# DDR3_2.net
KiCad netlist of a schematic drawn in Altium Designer
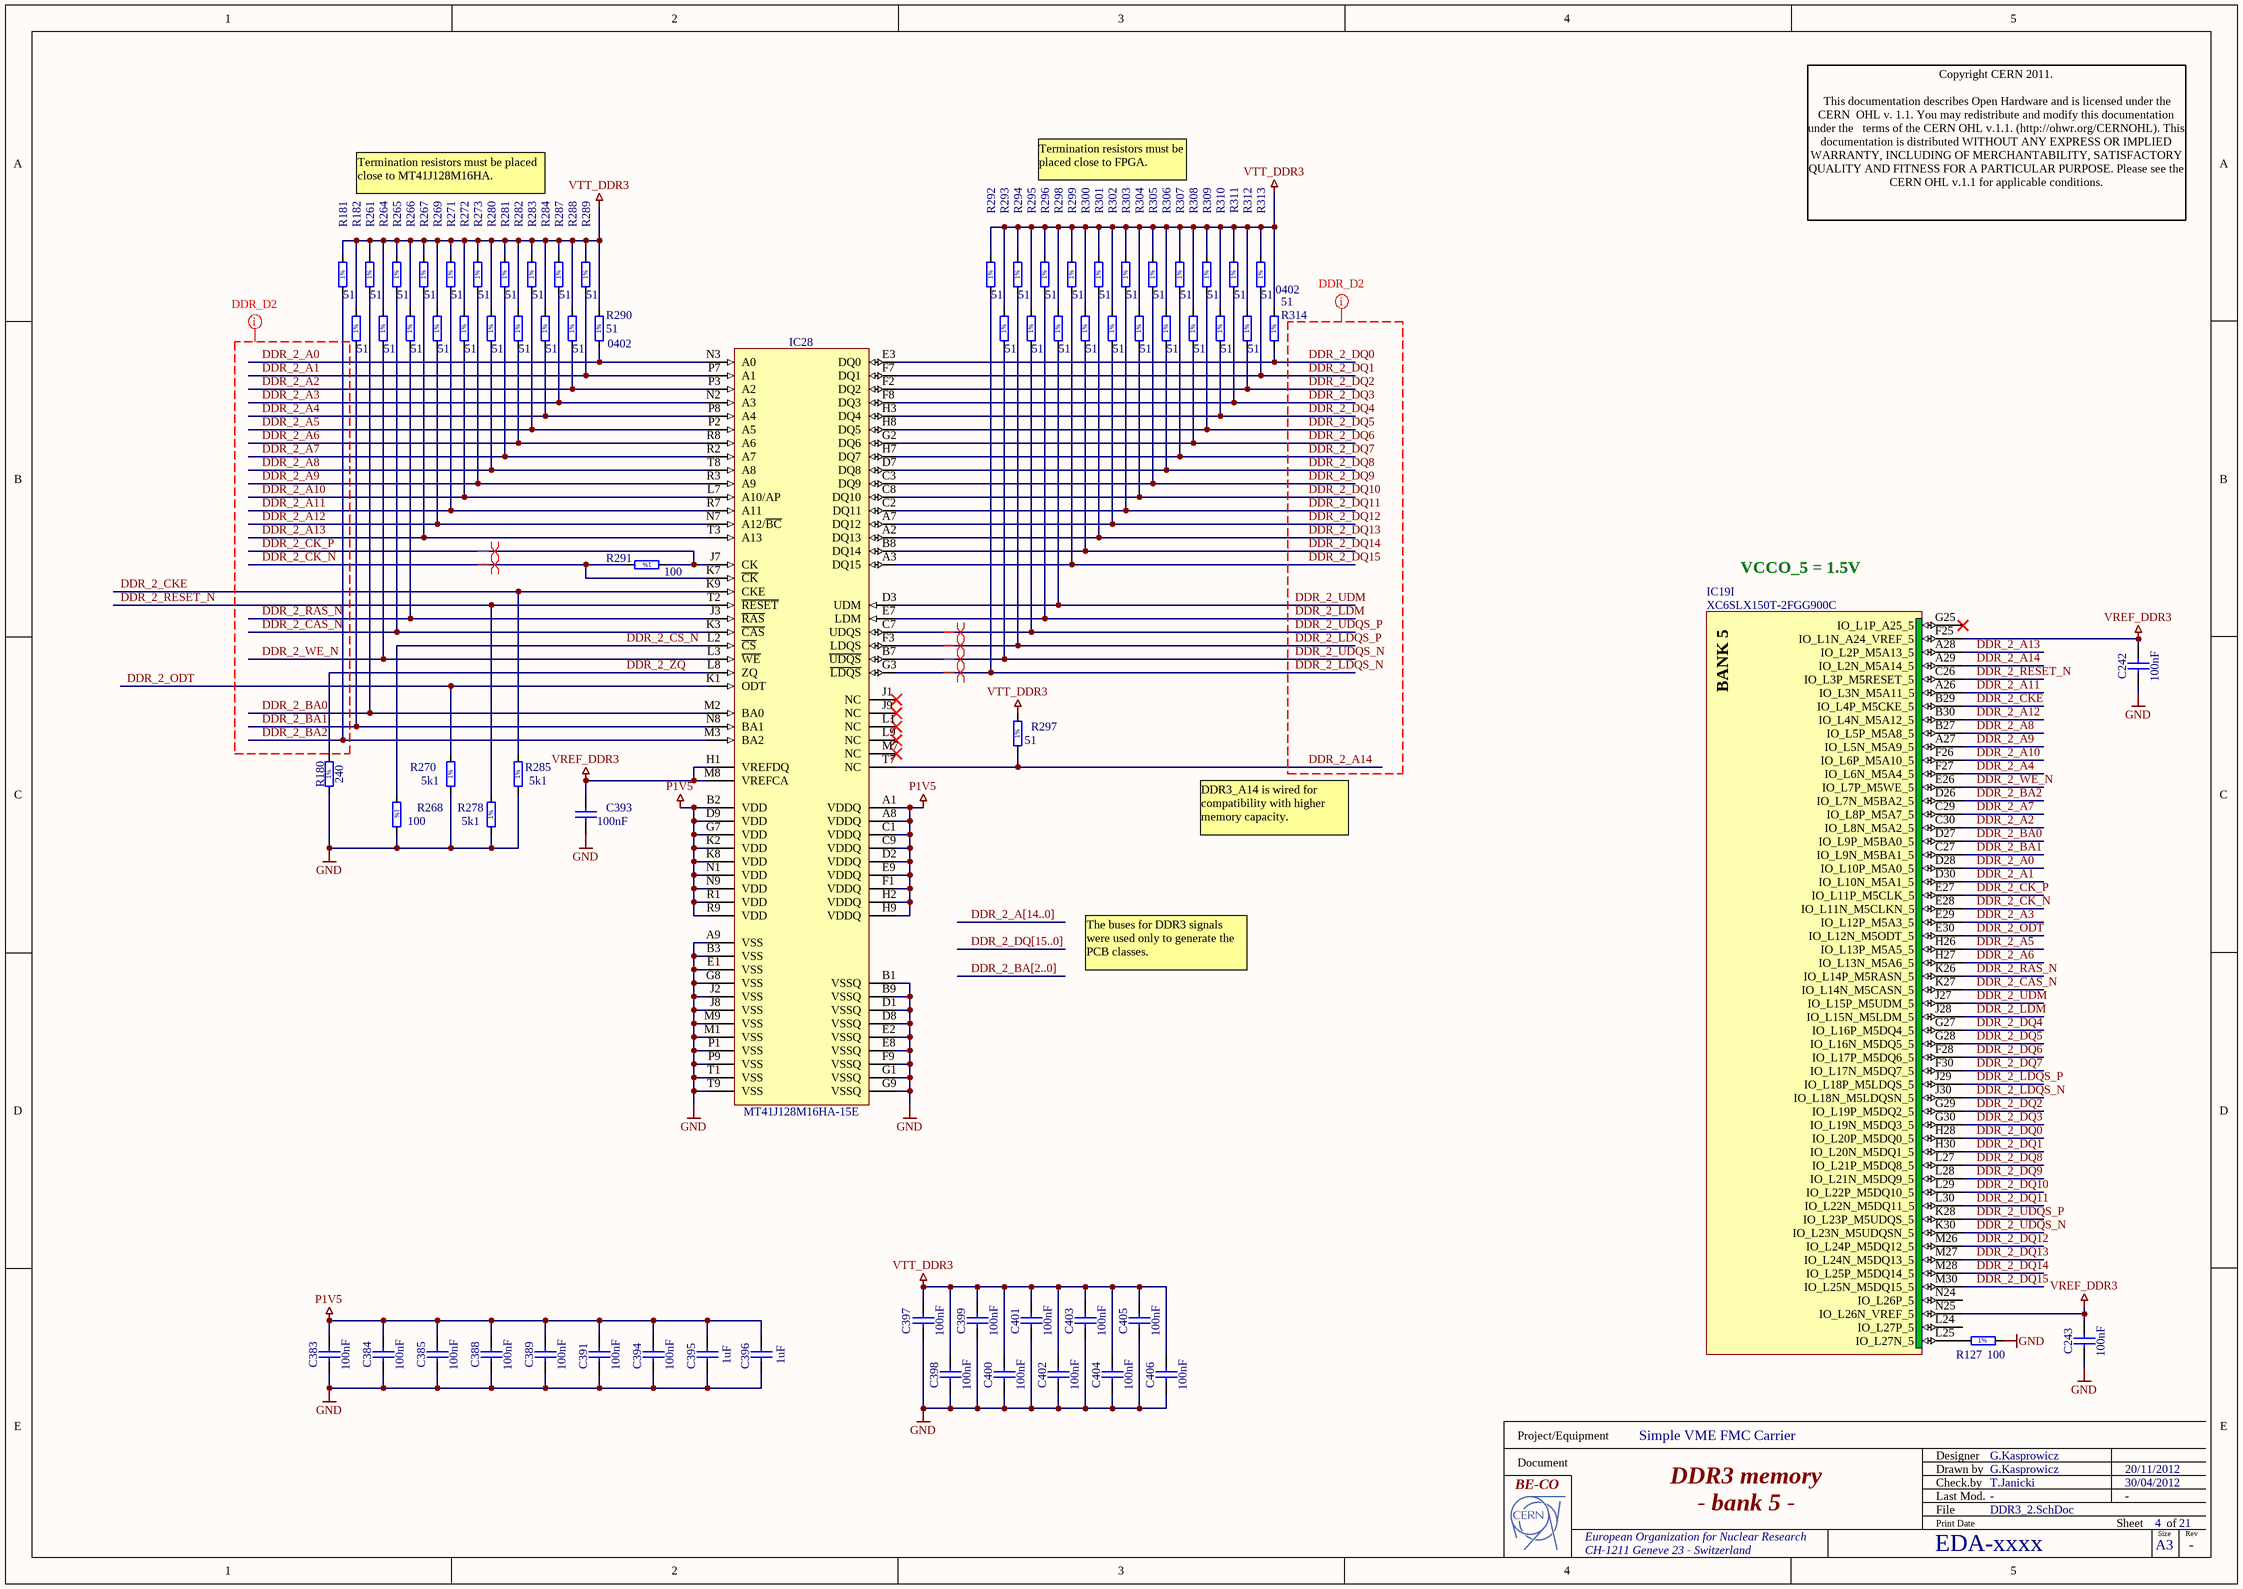
[diagram p0: DDR3_2.SchDoc]

(export (version "E")
  (design (tool "Eeschema 10.0.6"))
  (components
    (comp (ref "C242")
      (value "100nF")
      (footprint "CAPC1005X55N")
      (description "Non-polarised capacitor")
      (fields
        (field (name "PART NUMBER") "CC0402_100NF_16V_10%_X7R")
        (field (name "VOLTAGE") "16V")
        (field (name "AUTHOR") "CERN DEM JLC")
      )
      (libsource (lib "Capacitors") (part "Capacitor - non polarized"))
    )
    (comp (ref "C243")
      (value "100nF")
      (footprint "CAPC1005X55N")
      (description "Non-polarised capacitor")
      (fields
        (field (name "PART NUMBER") "CC0402_100NF_16V_10%_X7R")
        (field (name "VOLTAGE") "16V")
        (field (name "AUTHOR") "CERN DEM JLC")
      )
      (libsource (lib "Capacitors") (part "Capacitor - non polarized"))
    )
    (comp (ref "C383")
      (value "100nF")
      (footprint "CAPC1005X55N")
      (description "Non-polarised capacitor")
      (fields
        (field (name "PART NUMBER") "CC0402_100NF_16V_10%_X7R")
        (field (name "VOLTAGE") "16V")
        (field (name "AUTHOR") "CERN DEM JLC")
      )
      (libsource (lib "Capacitors") (part "Capacitor - non polarized"))
    )
    (comp (ref "C384")
      (value "100nF")
      (footprint "CAPC1005X55N")
      (description "Non-polarised capacitor")
      (fields
        (field (name "PART NUMBER") "CC0402_100NF_16V_10%_X7R")
        (field (name "VOLTAGE") "16V")
        (field (name "AUTHOR") "CERN DEM JLC")
      )
      (libsource (lib "Capacitors") (part "Capacitor - non polarized"))
    )
    (comp (ref "C385")
      (value "100nF")
      (footprint "CAPC1005X55N")
      (description "Non-polarised capacitor")
      (fields
        (field (name "PART NUMBER") "CC0402_100NF_16V_10%_X7R")
        (field (name "VOLTAGE") "16V")
        (field (name "AUTHOR") "CERN DEM JLC")
      )
      (libsource (lib "Capacitors") (part "Capacitor - non polarized"))
    )
    (comp (ref "C388")
      (value "100nF")
      (footprint "CAPC1005X55N")
      (description "Non-polarised capacitor")
      (fields
        (field (name "PART NUMBER") "CC0402_100NF_16V_10%_X7R")
        (field (name "VOLTAGE") "16V")
        (field (name "AUTHOR") "CERN DEM JLC")
      )
      (libsource (lib "Capacitors") (part "Capacitor - non polarized"))
    )
    (comp (ref "C389")
      (value "100nF")
      (footprint "CAPC1005X55N")
      (description "Non-polarised capacitor")
      (fields
        (field (name "PART NUMBER") "CC0402_100NF_16V_10%_X7R")
        (field (name "VOLTAGE") "16V")
        (field (name "AUTHOR") "CERN DEM JLC")
      )
      (libsource (lib "Capacitors") (part "Capacitor - non polarized"))
    )
    (comp (ref "C391")
      (value "100nF")
      (footprint "CAPC1005X55N")
      (description "Non-polarised capacitor")
      (fields
        (field (name "PART NUMBER") "CC0402_100NF_16V_10%_X7R")
        (field (name "VOLTAGE") "16V")
        (field (name "AUTHOR") "CERN DEM JLC")
      )
      (libsource (lib "Capacitors") (part "Capacitor - non polarized"))
    )
    (comp (ref "C393")
      (value "100nF")
      (footprint "CAPC1005X55N")
      (description "Non-polarised capacitor")
      (fields
        (field (name "PART NUMBER") "CC0402_100NF_16V_10%_X7R")
        (field (name "VOLTAGE") "16V")
        (field (name "AUTHOR") "CERN DEM JLC")
      )
      (libsource (lib "Capacitors") (part "Capacitor - non polarized"))
    )
    (comp (ref "C394")
      (value "100nF")
      (footprint "CAPC1005X55N")
      (description "Non-polarised capacitor")
      (fields
        (field (name "PART NUMBER") "CC0402_100NF_16V_10%_X7R")
        (field (name "VOLTAGE") "16V")
        (field (name "AUTHOR") "CERN DEM JLC")
      )
      (libsource (lib "Capacitors") (part "Capacitor - non polarized"))
    )
    (comp (ref "C395")
      (value "1uF")
      (footprint "CAPC1608X87N")
      (description "Non-polarised capacitor")
      (fields
        (field (name "PART NUMBER") "CC0603_1UF_16V_10%_X7R")
        (field (name "VOLTAGE") "16V")
        (field (name "AUTHOR") "CERN DEM JLC")
      )
      (libsource (lib "Capacitors") (part "Capacitor - non polarized"))
    )
    (comp (ref "C396")
      (value "1uF")
      (footprint "CAPC1608X87N")
      (description "Non-polarised capacitor")
      (fields
        (field (name "PART NUMBER") "CC0603_1UF_16V_10%_X7R")
        (field (name "VOLTAGE") "16V")
        (field (name "AUTHOR") "CERN DEM JLC")
      )
      (libsource (lib "Capacitors") (part "Capacitor - non polarized"))
    )
    (comp (ref "C397")
      (value "100nF")
      (footprint "CAPC1005X55N")
      (description "Non-polarised capacitor")
      (fields
        (field (name "PART NUMBER") "CC0402_100NF_16V_10%_X7R")
        (field (name "VOLTAGE") "16V")
        (field (name "AUTHOR") "CERN DEM JLC")
      )
      (libsource (lib "Capacitors") (part "Capacitor - non polarized"))
    )
    (comp (ref "C398")
      (value "100nF")
      (footprint "CAPC1005X55N")
      (description "Non-polarised capacitor")
      (fields
        (field (name "PART NUMBER") "CC0402_100NF_16V_10%_X7R")
        (field (name "VOLTAGE") "16V")
        (field (name "AUTHOR") "CERN DEM JLC")
      )
      (libsource (lib "Capacitors") (part "Capacitor - non polarized"))
    )
    (comp (ref "C399")
      (value "100nF")
      (footprint "CAPC1005X55N")
      (description "Non-polarised capacitor")
      (fields
        (field (name "PART NUMBER") "CC0402_100NF_16V_10%_X7R")
        (field (name "VOLTAGE") "16V")
        (field (name "AUTHOR") "CERN DEM JLC")
      )
      (libsource (lib "Capacitors") (part "Capacitor - non polarized"))
    )
    (comp (ref "C400")
      (value "100nF")
      (footprint "CAPC1005X55N")
      (description "Non-polarised capacitor")
      (fields
        (field (name "PART NUMBER") "CC0402_100NF_16V_10%_X7R")
        (field (name "VOLTAGE") "16V")
        (field (name "AUTHOR") "CERN DEM JLC")
      )
      (libsource (lib "Capacitors") (part "Capacitor - non polarized"))
    )
    (comp (ref "C401")
      (value "100nF")
      (footprint "CAPC1005X55N")
      (description "Non-polarised capacitor")
      (fields
        (field (name "PART NUMBER") "CC0402_100NF_16V_10%_X7R")
        (field (name "VOLTAGE") "16V")
        (field (name "AUTHOR") "CERN DEM JLC")
      )
      (libsource (lib "Capacitors") (part "Capacitor - non polarized"))
    )
    (comp (ref "C402")
      (value "100nF")
      (footprint "CAPC1005X55N")
      (description "Non-polarised capacitor")
      (fields
        (field (name "PART NUMBER") "CC0402_100NF_16V_10%_X7R")
        (field (name "VOLTAGE") "16V")
        (field (name "AUTHOR") "CERN DEM JLC")
      )
      (libsource (lib "Capacitors") (part "Capacitor - non polarized"))
    )
    (comp (ref "C403")
      (value "100nF")
      (footprint "CAPC1005X55N")
      (description "Non-polarised capacitor")
      (fields
        (field (name "PART NUMBER") "CC0402_100NF_16V_10%_X7R")
        (field (name "VOLTAGE") "16V")
        (field (name "AUTHOR") "CERN DEM JLC")
      )
      (libsource (lib "Capacitors") (part "Capacitor - non polarized"))
    )
    (comp (ref "C404")
      (value "100nF")
      (footprint "CAPC1005X55N")
      (description "Non-polarised capacitor")
      (fields
        (field (name "PART NUMBER") "CC0402_100NF_16V_10%_X7R")
        (field (name "VOLTAGE") "16V")
        (field (name "AUTHOR") "CERN DEM JLC")
      )
      (libsource (lib "Capacitors") (part "Capacitor - non polarized"))
    )
    (comp (ref "C405")
      (value "100nF")
      (footprint "CAPC1005X55N")
      (description "Non-polarised capacitor")
      (fields
        (field (name "PART NUMBER") "CC0402_100NF_16V_10%_X7R")
        (field (name "VOLTAGE") "16V")
        (field (name "AUTHOR") "CERN DEM JLC")
      )
      (libsource (lib "Capacitors") (part "Capacitor - non polarized"))
    )
    (comp (ref "C406")
      (value "100nF")
      (footprint "CAPC1005X55N")
      (description "Non-polarised capacitor")
      (fields
        (field (name "PART NUMBER") "CC0402_100NF_16V_10%_X7R")
        (field (name "VOLTAGE") "16V")
        (field (name "AUTHOR") "CERN DEM JLC")
      )
      (libsource (lib "Capacitors") (part "Capacitor - non polarized"))
    )
    (comp (ref "IC19")
      (value "XC6SLX150T-2FGG900C")
      (footprint "BGA900C100P30X30_3100X3100X260")
      (description "SPARTAN-6, FPGA, 900-Ball BGA, Commercial Grade, Pb-Free")
      (fields (field (name "MANUFACTURER") "XILINX") (field (name "AUTHOR") "CERN DEM JLC"))
      (libsource (lib "ICs And Semiconductors") (part "XC6SLX150T-2FGG900C"))
    )
    (comp (ref "IC28")
      (value "MT41J128M16HA-15E")
      (footprint "BGA96C80P9X16_900X1400X120")
      (description "16 Meg x 16 x 8 Banks DDR3 SDRAM")
      (fields (field (name "MANUFACTURER") "MICRON TECHNOLOGY") (field (name "AUTHOR") "CERN DEM JLC"))
      (libsource (lib "ICs And Semiconductors") (part "MT41J128M16HA"))
    )
    (comp (ref "R127")
      (value "100")
      (footprint "RESC1608X55N")
      (description "Resistor - 1%")
      (fields
        (field (name "PART NUMBER") "R0603_100R_1%_0.1W_100PPM")
        (field (name "POWER") "0.1W")
        (field (name "AUTHOR") "CERN DEM JLC")
      )
      (libsource (lib "Resistors") (part "Resistor - 1%"))
    )
    (comp (ref "R180")
      (value "240")
      (footprint "RESC1608X55N")
      (description "Resistor - 1%")
      (fields
        (field (name "PART NUMBER") "R0603_240R_1%_0.1W_100PPM")
        (field (name "POWER") "0.1W")
        (field (name "AUTHOR") "CERN DEM JLC")
      )
      (libsource (lib "Resistors") (part "Resistor - 1%"))
    )
    (comp (ref "R181")
      (value "51")
      (footprint "RESC1005X40N")
      (description "Resistor - 1%")
      (fields
        (field (name "PART NUMBER") "R0402_51R_1%_0.0625W_100PPM")
        (field (name "POWER") "0.0625W")
        (field (name "AUTHOR") "CERN DEM JLC")
      )
      (libsource (lib "Resistors") (part "Resistor - 1%"))
    )
    (comp (ref "R182")
      (value "51")
      (footprint "RESC1005X40N")
      (description "Resistor - 1%")
      (fields
        (field (name "PART NUMBER") "R0402_51R_1%_0.0625W_100PPM")
        (field (name "POWER") "0.0625W")
        (field (name "AUTHOR") "CERN DEM JLC")
      )
      (libsource (lib "Resistors") (part "Resistor - 1%"))
    )
    (comp (ref "R261")
      (value "51")
      (footprint "RESC1005X40N")
      (description "Resistor - 1%")
      (fields
        (field (name "PART NUMBER") "R0402_51R_1%_0.0625W_100PPM")
        (field (name "POWER") "0.0625W")
        (field (name "AUTHOR") "CERN DEM JLC")
      )
      (libsource (lib "Resistors") (part "Resistor - 1%"))
    )
    (comp (ref "R264")
      (value "51")
      (footprint "RESC1005X40N")
      (description "Resistor - 1%")
      (fields
        (field (name "PART NUMBER") "R0402_51R_1%_0.0625W_100PPM")
        (field (name "POWER") "0.0625W")
        (field (name "AUTHOR") "CERN DEM JLC")
      )
      (libsource (lib "Resistors") (part "Resistor - 1%"))
    )
    (comp (ref "R265")
      (value "51")
      (footprint "RESC1005X40N")
      (description "Resistor - 1%")
      (fields
        (field (name "PART NUMBER") "R0402_51R_1%_0.0625W_100PPM")
        (field (name "POWER") "0.0625W")
        (field (name "AUTHOR") "CERN DEM JLC")
      )
      (libsource (lib "Resistors") (part "Resistor - 1%"))
    )
    (comp (ref "R266")
      (value "51")
      (footprint "RESC1005X40N")
      (description "Resistor - 1%")
      (fields
        (field (name "PART NUMBER") "R0402_51R_1%_0.0625W_100PPM")
        (field (name "POWER") "0.0625W")
        (field (name "AUTHOR") "CERN DEM JLC")
      )
      (libsource (lib "Resistors") (part "Resistor - 1%"))
    )
    (comp (ref "R267")
      (value "51")
      (footprint "RESC1005X40N")
      (description "Resistor - 1%")
      (fields
        (field (name "PART NUMBER") "R0402_51R_1%_0.0625W_100PPM")
        (field (name "POWER") "0.0625W")
        (field (name "AUTHOR") "CERN DEM JLC")
      )
      (libsource (lib "Resistors") (part "Resistor - 1%"))
    )
    (comp (ref "R268")
      (value "100")
      (footprint "RESC1608X55N")
      (description "Resistor - 1%")
      (fields
        (field (name "PART NUMBER") "R0603_100R_1%_0.1W_100PPM")
        (field (name "POWER") "0.1W")
        (field (name "AUTHOR") "CERN DEM JLC")
      )
      (libsource (lib "Resistors") (part "Resistor - 1%"))
    )
    (comp (ref "R269")
      (value "51")
      (footprint "RESC1005X40N")
      (description "Resistor - 1%")
      (fields
        (field (name "PART NUMBER") "R0402_51R_1%_0.0625W_100PPM")
        (field (name "POWER") "0.0625W")
        (field (name "AUTHOR") "CERN DEM JLC")
      )
      (libsource (lib "Resistors") (part "Resistor - 1%"))
    )
    (comp (ref "R270")
      (value "5k1")
      (footprint "RESC1608X55N")
      (description "Resistor - 1%")
      (fields
        (field (name "PART NUMBER") "R0603_5K1_1%_0.1W_100PPM")
        (field (name "POWER") "0.1W")
        (field (name "AUTHOR") "CERN DEM JLC")
      )
      (libsource (lib "Resistors") (part "Resistor - 1%"))
    )
    (comp (ref "R271")
      (value "51")
      (footprint "RESC1005X40N")
      (description "Resistor - 1%")
      (fields
        (field (name "PART NUMBER") "R0402_51R_1%_0.0625W_100PPM")
        (field (name "POWER") "0.0625W")
        (field (name "AUTHOR") "CERN DEM JLC")
      )
      (libsource (lib "Resistors") (part "Resistor - 1%"))
    )
    (comp (ref "R272")
      (value "51")
      (footprint "RESC1005X40N")
      (description "Resistor - 1%")
      (fields
        (field (name "PART NUMBER") "R0402_51R_1%_0.0625W_100PPM")
        (field (name "POWER") "0.0625W")
        (field (name "AUTHOR") "CERN DEM JLC")
      )
      (libsource (lib "Resistors") (part "Resistor - 1%"))
    )
    (comp (ref "R273")
      (value "51")
      (footprint "RESC1005X40N")
      (description "Resistor - 1%")
      (fields
        (field (name "PART NUMBER") "R0402_51R_1%_0.0625W_100PPM")
        (field (name "POWER") "0.0625W")
        (field (name "AUTHOR") "CERN DEM JLC")
      )
      (libsource (lib "Resistors") (part "Resistor - 1%"))
    )
    (comp (ref "R278")
      (value "5k1")
      (footprint "RESC1608X55N")
      (description "Resistor - 1%")
      (fields
        (field (name "PART NUMBER") "R0603_5K1_1%_0.1W_100PPM")
        (field (name "POWER") "0.1W")
        (field (name "AUTHOR") "CERN DEM JLC")
      )
      (libsource (lib "Resistors") (part "Resistor - 1%"))
    )
    (comp (ref "R280")
      (value "51")
      (footprint "RESC1005X40N")
      (description "Resistor - 1%")
      (fields
        (field (name "PART NUMBER") "R0402_51R_1%_0.0625W_100PPM")
        (field (name "POWER") "0.0625W")
        (field (name "AUTHOR") "CERN DEM JLC")
      )
      (libsource (lib "Resistors") (part "Resistor - 1%"))
    )
    (comp (ref "R281")
      (value "51")
      (footprint "RESC1005X40N")
      (description "Resistor - 1%")
      (fields
        (field (name "PART NUMBER") "R0402_51R_1%_0.0625W_100PPM")
        (field (name "POWER") "0.0625W")
        (field (name "AUTHOR") "CERN DEM JLC")
      )
      (libsource (lib "Resistors") (part "Resistor - 1%"))
    )
    (comp (ref "R282")
      (value "51")
      (footprint "RESC1005X40N")
      (description "Resistor - 1%")
      (fields
        (field (name "PART NUMBER") "R0402_51R_1%_0.0625W_100PPM")
        (field (name "POWER") "0.0625W")
        (field (name "AUTHOR") "CERN DEM JLC")
      )
      (libsource (lib "Resistors") (part "Resistor - 1%"))
    )
    (comp (ref "R283")
      (value "51")
      (footprint "RESC1005X40N")
      (description "Resistor - 1%")
      (fields
        (field (name "PART NUMBER") "R0402_51R_1%_0.0625W_100PPM")
        (field (name "POWER") "0.0625W")
        (field (name "AUTHOR") "CERN DEM JLC")
      )
      (libsource (lib "Resistors") (part "Resistor - 1%"))
    )
    (comp (ref "R284")
      (value "51")
      (footprint "RESC1005X40N")
      (description "Resistor - 1%")
      (fields
        (field (name "PART NUMBER") "R0402_51R_1%_0.0625W_100PPM")
        (field (name "POWER") "0.0625W")
        (field (name "AUTHOR") "CERN DEM JLC")
      )
      (libsource (lib "Resistors") (part "Resistor - 1%"))
    )
    (comp (ref "R285")
      (value "5k1")
      (footprint "RESC1608X55N")
      (description "Resistor - 1%")
      (fields
        (field (name "PART NUMBER") "R0603_5K1_1%_0.1W_100PPM")
        (field (name "POWER") "0.1W")
        (field (name "AUTHOR") "CERN DEM JLC")
      )
      (libsource (lib "Resistors") (part "Resistor - 1%"))
    )
    (comp (ref "R287")
      (value "51")
      (footprint "RESC1005X40N")
      (description "Resistor - 1%")
      (fields
        (field (name "PART NUMBER") "R0402_51R_1%_0.0625W_100PPM")
        (field (name "POWER") "0.0625W")
        (field (name "AUTHOR") "CERN DEM JLC")
      )
      (libsource (lib "Resistors") (part "Resistor - 1%"))
    )
    (comp (ref "R288")
      (value "51")
      (footprint "RESC1005X40N")
      (description "Resistor - 1%")
      (fields
        (field (name "PART NUMBER") "R0402_51R_1%_0.0625W_100PPM")
        (field (name "POWER") "0.0625W")
        (field (name "AUTHOR") "CERN DEM JLC")
      )
      (libsource (lib "Resistors") (part "Resistor - 1%"))
    )
    (comp (ref "R289")
      (value "51")
      (footprint "RESC1005X40N")
      (description "Resistor - 1%")
      (fields
        (field (name "PART NUMBER") "R0402_51R_1%_0.0625W_100PPM")
        (field (name "POWER") "0.0625W")
        (field (name "AUTHOR") "CERN DEM JLC")
      )
      (libsource (lib "Resistors") (part "Resistor - 1%"))
    )
    (comp (ref "R290")
      (value "51")
      (footprint "RESC1005X40N")
      (description "Resistor - 1%")
      (fields
        (field (name "PART NUMBER") "R0402_51R_1%_0.0625W_100PPM")
        (field (name "POWER") "0.0625W")
        (field (name "CASE") "0402")
        (field (name "AUTHOR") "CERN DEM JLC")
      )
      (libsource (lib "Resistors") (part "Resistor - 1%"))
    )
    (comp (ref "R291")
      (value "100")
      (footprint "RESC1608X55N")
      (description "Resistor - 1%")
      (fields
        (field (name "PART NUMBER") "R0603_100R_1%_0.1W_100PPM")
        (field (name "POWER") "0.1W")
        (field (name "AUTHOR") "CERN DEM JLC")
      )
      (libsource (lib "Resistors") (part "Resistor - 1%"))
    )
    (comp (ref "R292")
      (value "51")
      (footprint "RESC1005X40N")
      (description "Resistor - 1%")
      (fields
        (field (name "PART NUMBER") "R0402_51R_1%_0.0625W_100PPM")
        (field (name "POWER") "0.0625W")
        (field (name "AUTHOR") "CERN DEM JLC")
      )
      (libsource (lib "Resistors") (part "Resistor - 1%"))
    )
    (comp (ref "R293")
      (value "51")
      (footprint "RESC1005X40N")
      (description "Resistor - 1%")
      (fields
        (field (name "PART NUMBER") "R0402_51R_1%_0.0625W_100PPM")
        (field (name "POWER") "0.0625W")
        (field (name "AUTHOR") "CERN DEM JLC")
      )
      (libsource (lib "Resistors") (part "Resistor - 1%"))
    )
    (comp (ref "R294")
      (value "51")
      (footprint "RESC1005X40N")
      (description "Resistor - 1%")
      (fields
        (field (name "PART NUMBER") "R0402_51R_1%_0.0625W_100PPM")
        (field (name "POWER") "0.0625W")
        (field (name "AUTHOR") "CERN DEM JLC")
      )
      (libsource (lib "Resistors") (part "Resistor - 1%"))
    )
    (comp (ref "R295")
      (value "51")
      (footprint "RESC1005X40N")
      (description "Resistor - 1%")
      (fields
        (field (name "PART NUMBER") "R0402_51R_1%_0.0625W_100PPM")
        (field (name "POWER") "0.0625W")
        (field (name "AUTHOR") "CERN DEM JLC")
      )
      (libsource (lib "Resistors") (part "Resistor - 1%"))
    )
    (comp (ref "R296")
      (value "51")
      (footprint "RESC1005X40N")
      (description "Resistor - 1%")
      (fields
        (field (name "PART NUMBER") "R0402_51R_1%_0.0625W_100PPM")
        (field (name "POWER") "0.0625W")
        (field (name "AUTHOR") "CERN DEM JLC")
      )
      (libsource (lib "Resistors") (part "Resistor - 1%"))
    )
    (comp (ref "R297")
      (value "51")
      (footprint "RESC1005X40N")
      (description "Resistor - 1%")
      (fields
        (field (name "PART NUMBER") "R0402_51R_1%_0.0625W_100PPM")
        (field (name "POWER") "0.0625W")
        (field (name "AUTHOR") "CERN DEM JLC")
      )
      (libsource (lib "Resistors") (part "Resistor - 1%"))
    )
    (comp (ref "R298")
      (value "51")
      (footprint "RESC1005X40N")
      (description "Resistor - 1%")
      (fields
        (field (name "PART NUMBER") "R0402_51R_1%_0.0625W_100PPM")
        (field (name "POWER") "0.0625W")
        (field (name "AUTHOR") "CERN DEM JLC")
      )
      (libsource (lib "Resistors") (part "Resistor - 1%"))
    )
    (comp (ref "R299")
      (value "51")
      (footprint "RESC1005X40N")
      (description "Resistor - 1%")
      (fields
        (field (name "PART NUMBER") "R0402_51R_1%_0.0625W_100PPM")
        (field (name "POWER") "0.0625W")
        (field (name "AUTHOR") "CERN DEM JLC")
      )
      (libsource (lib "Resistors") (part "Resistor - 1%"))
    )
    (comp (ref "R300")
      (value "51")
      (footprint "RESC1005X40N")
      (description "Resistor - 1%")
      (fields
        (field (name "PART NUMBER") "R0402_51R_1%_0.0625W_100PPM")
        (field (name "POWER") "0.0625W")
        (field (name "AUTHOR") "CERN DEM JLC")
      )
      (libsource (lib "Resistors") (part "Resistor - 1%"))
    )
    (comp (ref "R301")
      (value "51")
      (footprint "RESC1005X40N")
      (description "Resistor - 1%")
      (fields
        (field (name "PART NUMBER") "R0402_51R_1%_0.0625W_100PPM")
        (field (name "POWER") "0.0625W")
        (field (name "AUTHOR") "CERN DEM JLC")
      )
      (libsource (lib "Resistors") (part "Resistor - 1%"))
    )
    (comp (ref "R302")
      (value "51")
      (footprint "RESC1005X40N")
      (description "Resistor - 1%")
      (fields
        (field (name "PART NUMBER") "R0402_51R_1%_0.0625W_100PPM")
        (field (name "POWER") "0.0625W")
        (field (name "AUTHOR") "CERN DEM JLC")
      )
      (libsource (lib "Resistors") (part "Resistor - 1%"))
    )
    (comp (ref "R303")
      (value "51")
      (footprint "RESC1005X40N")
      (description "Resistor - 1%")
      (fields
        (field (name "PART NUMBER") "R0402_51R_1%_0.0625W_100PPM")
        (field (name "POWER") "0.0625W")
        (field (name "AUTHOR") "CERN DEM JLC")
      )
      (libsource (lib "Resistors") (part "Resistor - 1%"))
    )
    (comp (ref "R304")
      (value "51")
      (footprint "RESC1005X40N")
      (description "Resistor - 1%")
      (fields
        (field (name "PART NUMBER") "R0402_51R_1%_0.0625W_100PPM")
        (field (name "POWER") "0.0625W")
        (field (name "AUTHOR") "CERN DEM JLC")
      )
      (libsource (lib "Resistors") (part "Resistor - 1%"))
    )
    (comp (ref "R305")
      (value "51")
      (footprint "RESC1005X40N")
      (description "Resistor - 1%")
      (fields
        (field (name "PART NUMBER") "R0402_51R_1%_0.0625W_100PPM")
        (field (name "POWER") "0.0625W")
        (field (name "AUTHOR") "CERN DEM JLC")
      )
      (libsource (lib "Resistors") (part "Resistor - 1%"))
    )
    (comp (ref "R306")
      (value "51")
      (footprint "RESC1005X40N")
      (description "Resistor - 1%")
      (fields
        (field (name "PART NUMBER") "R0402_51R_1%_0.0625W_100PPM")
        (field (name "POWER") "0.0625W")
        (field (name "AUTHOR") "CERN DEM JLC")
      )
      (libsource (lib "Resistors") (part "Resistor - 1%"))
    )
    (comp (ref "R307")
      (value "51")
      (footprint "RESC1005X40N")
      (description "Resistor - 1%")
      (fields
        (field (name "PART NUMBER") "R0402_51R_1%_0.0625W_100PPM")
        (field (name "POWER") "0.0625W")
        (field (name "AUTHOR") "CERN DEM JLC")
      )
      (libsource (lib "Resistors") (part "Resistor - 1%"))
    )
    (comp (ref "R308")
      (value "51")
      (footprint "RESC1005X40N")
      (description "Resistor - 1%")
      (fields
        (field (name "PART NUMBER") "R0402_51R_1%_0.0625W_100PPM")
        (field (name "POWER") "0.0625W")
        (field (name "AUTHOR") "CERN DEM JLC")
      )
      (libsource (lib "Resistors") (part "Resistor - 1%"))
    )
    (comp (ref "R309")
      (value "51")
      (footprint "RESC1005X40N")
      (description "Resistor - 1%")
      (fields
        (field (name "PART NUMBER") "R0402_51R_1%_0.0625W_100PPM")
        (field (name "POWER") "0.0625W")
        (field (name "AUTHOR") "CERN DEM JLC")
      )
      (libsource (lib "Resistors") (part "Resistor - 1%"))
    )
    (comp (ref "R310")
      (value "51")
      (footprint "RESC1005X40N")
      (description "Resistor - 1%")
      (fields
        (field (name "PART NUMBER") "R0402_51R_1%_0.0625W_100PPM")
        (field (name "POWER") "0.0625W")
        (field (name "AUTHOR") "CERN DEM JLC")
      )
      (libsource (lib "Resistors") (part "Resistor - 1%"))
    )
    (comp (ref "R311")
      (value "51")
      (footprint "RESC1005X40N")
      (description "Resistor - 1%")
      (fields
        (field (name "PART NUMBER") "R0402_51R_1%_0.0625W_100PPM")
        (field (name "POWER") "0.0625W")
        (field (name "AUTHOR") "CERN DEM JLC")
      )
      (libsource (lib "Resistors") (part "Resistor - 1%"))
    )
    (comp (ref "R312")
      (value "51")
      (footprint "RESC1005X40N")
      (description "Resistor - 1%")
      (fields
        (field (name "PART NUMBER") "R0402_51R_1%_0.0625W_100PPM")
        (field (name "POWER") "0.0625W")
        (field (name "AUTHOR") "CERN DEM JLC")
      )
      (libsource (lib "Resistors") (part "Resistor - 1%"))
    )
    (comp (ref "R313")
      (value "51")
      (footprint "RESC1005X40N")
      (description "Resistor - 1%")
      (fields
        (field (name "PART NUMBER") "R0402_51R_1%_0.0625W_100PPM")
        (field (name "POWER") "0.0625W")
        (field (name "AUTHOR") "CERN DEM JLC")
      )
      (libsource (lib "Resistors") (part "Resistor - 1%"))
    )
    (comp (ref "R314")
      (value "51")
      (footprint "RESC1005X40N")
      (description "Resistor - 1%")
      (fields
        (field (name "PART NUMBER") "R0402_51R_1%_0.0625W_100PPM")
        (field (name "POWER") "0.0625W")
        (field (name "CASE") "0402")
        (field (name "AUTHOR") "CERN DEM JLC")
      )
      (libsource (lib "Resistors") (part "Resistor - 1%"))
    )
  )
  (nets
    (net (code "1") (name "/DDR_2_A0") (class "Default")
      (node (ref "IC19") (pin "D28") (pinfunction "IO_L10P_M5A0_5_D28") (pintype "bidirectional"))
      (node (ref "IC28") (pin "N3") (pinfunction "A0_N3") (pintype "input"))
      (node (ref "R290") (pin "1") (pinfunction "1_1") (pintype "passive"))
    )
    (net (code "2") (name "/DDR_2_A1") (class "Default")
      (node (ref "IC19") (pin "D30") (pinfunction "IO_L10N_M5A1_5_D30") (pintype "bidirectional"))
      (node (ref "IC28") (pin "P7") (pinfunction "A1_P7") (pintype "input"))
      (node (ref "R289") (pin "1") (pinfunction "1_1") (pintype "passive"))
    )
    (net (code "3") (name "/DDR_2_A2") (class "Default")
      (node (ref "IC19") (pin "C30") (pinfunction "IO_L8N_M5A2_5_C30") (pintype "bidirectional"))
      (node (ref "IC28") (pin "P3") (pinfunction "A2_P3") (pintype "input"))
      (node (ref "R288") (pin "1") (pinfunction "1_1") (pintype "passive"))
    )
    (net (code "4") (name "/DDR_2_A3") (class "Default")
      (node (ref "IC19") (pin "E29") (pinfunction "IO_L12P_M5A3_5_E29") (pintype "bidirectional"))
      (node (ref "IC28") (pin "N2") (pinfunction "A3_N2") (pintype "input"))
      (node (ref "R287") (pin "1") (pinfunction "1_1") (pintype "passive"))
    )
    (net (code "5") (name "/DDR_2_A4") (class "Default")
      (node (ref "IC19") (pin "F27") (pinfunction "IO_L6N_M5A4_5_F27") (pintype "bidirectional"))
      (node (ref "IC28") (pin "P8") (pinfunction "A4_P8") (pintype "input"))
      (node (ref "R284") (pin "1") (pinfunction "1_1") (pintype "passive"))
    )
    (net (code "6") (name "/DDR_2_A5") (class "Default")
      (node (ref "IC19") (pin "H26") (pinfunction "IO_L13P_M5A5_5_H26") (pintype "bidirectional"))
      (node (ref "IC28") (pin "P2") (pinfunction "A5_P2") (pintype "input"))
      (node (ref "R283") (pin "1") (pinfunction "1_1") (pintype "passive"))
    )
    (net (code "7") (name "/DDR_2_A6") (class "Default")
      (node (ref "IC19") (pin "H27") (pinfunction "IO_L13N_M5A6_5_H27") (pintype "bidirectional"))
      (node (ref "IC28") (pin "R8") (pinfunction "A6_R8") (pintype "input"))
      (node (ref "R282") (pin "1") (pinfunction "1_1") (pintype "passive"))
    )
    (net (code "8") (name "/DDR_2_A7") (class "Default")
      (node (ref "IC19") (pin "C29") (pinfunction "IO_L8P_M5A7_5_C29") (pintype "bidirectional"))
      (node (ref "IC28") (pin "R2") (pinfunction "A7_R2") (pintype "input"))
      (node (ref "R281") (pin "1") (pinfunction "1_1") (pintype "passive"))
    )
    (net (code "9") (name "/DDR_2_A8") (class "Default")
      (node (ref "IC19") (pin "B27") (pinfunction "IO_L5P_M5A8_5_B27") (pintype "bidirectional"))
      (node (ref "IC28") (pin "T8") (pinfunction "A8_T8") (pintype "input"))
      (node (ref "R280") (pin "1") (pinfunction "1_1") (pintype "passive"))
    )
    (net (code "10") (name "/DDR_2_A9") (class "Default")
      (node (ref "IC19") (pin "A27") (pinfunction "IO_L5N_M5A9_5_A27") (pintype "bidirectional"))
      (node (ref "IC28") (pin "R3") (pinfunction "A9_R3") (pintype "input"))
      (node (ref "R273") (pin "1") (pinfunction "1_1") (pintype "passive"))
    )
    (net (code "11") (name "/DDR_2_A10") (class "Default")
      (node (ref "IC19") (pin "F26") (pinfunction "IO_L6P_M5A10_5_F26") (pintype "bidirectional"))
      (node (ref "IC28") (pin "L7") (pinfunction "A10/AP_L7") (pintype "input"))
      (node (ref "R272") (pin "1") (pinfunction "1_1") (pintype "passive"))
    )
    (net (code "12") (name "/DDR_2_A11") (class "Default")
      (node (ref "IC19") (pin "A26") (pinfunction "IO_L3N_M5A11_5_A26") (pintype "bidirectional"))
      (node (ref "IC28") (pin "R7") (pinfunction "A11_R7") (pintype "input"))
      (node (ref "R271") (pin "1") (pinfunction "1_1") (pintype "passive"))
    )
    (net (code "13") (name "/DDR_2_A12") (class "Default")
      (node (ref "IC19") (pin "B30") (pinfunction "IO_L4N_M5A12_5_B30") (pintype "bidirectional"))
      (node (ref "IC28") (pin "N7") (pinfunction "A12/~{BC}_N7") (pintype "input"))
      (node (ref "R269") (pin "1") (pinfunction "1_1") (pintype "passive"))
    )
    (net (code "14") (name "/DDR_2_A13") (class "Default")
      (node (ref "IC19") (pin "A28") (pinfunction "IO_L2P_M5A13_5_A28") (pintype "bidirectional"))
      (node (ref "IC28") (pin "T3") (pinfunction "A13_T3") (pintype "input"))
      (node (ref "R267") (pin "1") (pinfunction "1_1") (pintype "passive"))
    )
    (net (code "15") (name "/DDR_2_A14") (class "Default")
      (node (ref "IC19") (pin "A29") (pinfunction "IO_L2N_M5A14_5_A29") (pintype "bidirectional"))
      (node (ref "IC28") (pin "T7") (pinfunction "NC_T7") (pintype "passive"))
      (node (ref "R297") (pin "1") (pinfunction "1_1") (pintype "passive"))
    )
    (net (code "17") (name "/DDR_2_BA0") (class "Default")
      (node (ref "IC19") (pin "D27") (pinfunction "IO_L9P_M5BA0_5_D27") (pintype "bidirectional"))
      (node (ref "IC28") (pin "M2") (pinfunction "BA0_M2") (pintype "input"))
      (node (ref "R261") (pin "1") (pinfunction "1_1") (pintype "passive"))
    )
    (net (code "18") (name "/DDR_2_BA1") (class "Default")
      (node (ref "IC19") (pin "C27") (pinfunction "IO_L9N_M5BA1_5_C27") (pintype "bidirectional"))
      (node (ref "IC28") (pin "N8") (pinfunction "BA1_N8") (pintype "input"))
      (node (ref "R182") (pin "1") (pinfunction "1_1") (pintype "passive"))
    )
    (net (code "19") (name "/DDR_2_BA2") (class "Default")
      (node (ref "IC19") (pin "D26") (pinfunction "IO_L7N_M5BA2_5_D26") (pintype "bidirectional"))
      (node (ref "IC28") (pin "M3") (pinfunction "BA2_M3") (pintype "input"))
      (node (ref "R181") (pin "1") (pinfunction "1_1") (pintype "passive"))
    )
    (net (code "21") (name "/DDR_2_CAS_N") (class "Default")
      (node (ref "IC19") (pin "K27") (pinfunction "IO_L14N_M5CASN_5_K27") (pintype "bidirectional"))
      (node (ref "IC28") (pin "K3") (pinfunction "CAS_K3") (pintype "input"))
      (node (ref "R265") (pin "1") (pinfunction "1_1") (pintype "passive"))
    )
    (net (code "22") (name "/DDR_2_CKE") (class "Default")
      (node (ref "IC19") (pin "B29") (pinfunction "IO_L4P_M5CKE_5_B29") (pintype "bidirectional"))
      (node (ref "IC28") (pin "K9") (pinfunction "CKE_K9") (pintype "input"))
      (node (ref "R285") (pin "2") (pinfunction "2_2") (pintype "passive"))
    )
    (net (code "23") (name "/DDR_2_CK_N") (class "Default")
      (node (ref "IC19") (pin "E28") (pinfunction "IO_L11N_M5CLKN_5_E28") (pintype "bidirectional"))
      (node (ref "IC28") (pin "K7") (pinfunction "CK_K7") (pintype "input"))
      (node (ref "R291") (pin "2") (pinfunction "2_2") (pintype "passive"))
    )
    (net (code "24") (name "/DDR_2_CK_P") (class "Default")
      (node (ref "IC19") (pin "E27") (pinfunction "IO_L11P_M5CLK_5_E27") (pintype "bidirectional"))
      (node (ref "IC28") (pin "J7") (pinfunction "CK_J7") (pintype "input"))
      (node (ref "R291") (pin "1") (pinfunction "1_1") (pintype "passive"))
    )
    (net (code "25") (name "/DDR_2_CS_N") (class "Default")
      (node (ref "IC28") (pin "L2") (pinfunction "CS_L2") (pintype "input"))
      (node (ref "R268") (pin "1") (pinfunction "1_1") (pintype "passive"))
    )
    (net (code "26") (name "/DDR_2_DQ0") (class "Default")
      (node (ref "IC19") (pin "H28") (pinfunction "IO_L20P_M5DQ0_5_H28") (pintype "bidirectional"))
      (node (ref "IC28") (pin "E3") (pinfunction "DQ0_E3") (pintype "bidirectional"))
      (node (ref "R314") (pin "1") (pinfunction "1_1") (pintype "passive"))
    )
    (net (code "27") (name "/DDR_2_DQ1") (class "Default")
      (node (ref "IC19") (pin "H30") (pinfunction "IO_L20N_M5DQ1_5_H30") (pintype "bidirectional"))
      (node (ref "IC28") (pin "F7") (pinfunction "DQ1_F7") (pintype "bidirectional"))
      (node (ref "R313") (pin "1") (pinfunction "1_1") (pintype "passive"))
    )
    (net (code "28") (name "/DDR_2_DQ2") (class "Default")
      (node (ref "IC19") (pin "G29") (pinfunction "IO_L19P_M5DQ2_5_G29") (pintype "bidirectional"))
      (node (ref "IC28") (pin "F2") (pinfunction "DQ2_F2") (pintype "bidirectional"))
      (node (ref "R312") (pin "1") (pinfunction "1_1") (pintype "passive"))
    )
    (net (code "29") (name "/DDR_2_DQ3") (class "Default")
      (node (ref "IC19") (pin "G30") (pinfunction "IO_L19N_M5DQ3_5_G30") (pintype "bidirectional"))
      (node (ref "IC28") (pin "F8") (pinfunction "DQ3_F8") (pintype "bidirectional"))
      (node (ref "R311") (pin "1") (pinfunction "1_1") (pintype "passive"))
    )
    (net (code "30") (name "/DDR_2_DQ4") (class "Default")
      (node (ref "IC19") (pin "G27") (pinfunction "IO_L16P_M5DQ4_5_G27") (pintype "bidirectional"))
      (node (ref "IC28") (pin "H3") (pinfunction "DQ4_H3") (pintype "bidirectional"))
      (node (ref "R310") (pin "1") (pinfunction "1_1") (pintype "passive"))
    )
    (net (code "31") (name "/DDR_2_DQ5") (class "Default")
      (node (ref "IC19") (pin "G28") (pinfunction "IO_L16N_M5DQ5_5_G28") (pintype "bidirectional"))
      (node (ref "IC28") (pin "H8") (pinfunction "DQ5_H8") (pintype "bidirectional"))
      (node (ref "R309") (pin "1") (pinfunction "1_1") (pintype "passive"))
    )
    (net (code "32") (name "/DDR_2_DQ6") (class "Default")
      (node (ref "IC19") (pin "F28") (pinfunction "IO_L17P_M5DQ6_5_F28") (pintype "bidirectional"))
      (node (ref "IC28") (pin "G2") (pinfunction "DQ6_G2") (pintype "bidirectional"))
      (node (ref "R308") (pin "1") (pinfunction "1_1") (pintype "passive"))
    )
    (net (code "33") (name "/DDR_2_DQ7") (class "Default")
      (node (ref "IC19") (pin "F30") (pinfunction "IO_L17N_M5DQ7_5_F30") (pintype "bidirectional"))
      (node (ref "IC28") (pin "H7") (pinfunction "DQ7_H7") (pintype "bidirectional"))
      (node (ref "R307") (pin "1") (pinfunction "1_1") (pintype "passive"))
    )
    (net (code "34") (name "/DDR_2_DQ8") (class "Default")
      (node (ref "IC19") (pin "L27") (pinfunction "IO_L21P_M5DQ8_5_L27") (pintype "bidirectional"))
      (node (ref "IC28") (pin "D7") (pinfunction "DQ8_D7") (pintype "bidirectional"))
      (node (ref "R306") (pin "1") (pinfunction "1_1") (pintype "passive"))
    )
    (net (code "35") (name "/DDR_2_DQ9") (class "Default")
      (node (ref "IC19") (pin "L28") (pinfunction "IO_L21N_M5DQ9_5_L28") (pintype "bidirectional"))
      (node (ref "IC28") (pin "C3") (pinfunction "DQ9_C3") (pintype "bidirectional"))
      (node (ref "R305") (pin "1") (pinfunction "1_1") (pintype "passive"))
    )
    (net (code "36") (name "/DDR_2_DQ10") (class "Default")
      (node (ref "IC19") (pin "L29") (pinfunction "IO_L22P_M5DQ10_5_L29") (pintype "bidirectional"))
      (node (ref "IC28") (pin "C8") (pinfunction "DQ10_C8") (pintype "bidirectional"))
      (node (ref "R304") (pin "1") (pinfunction "1_1") (pintype "passive"))
    )
    (net (code "37") (name "/DDR_2_DQ11") (class "Default")
      (node (ref "IC19") (pin "L30") (pinfunction "IO_L22N_M5DQ11_5_L30") (pintype "bidirectional"))
      (node (ref "IC28") (pin "C2") (pinfunction "DQ11_C2") (pintype "bidirectional"))
      (node (ref "R303") (pin "1") (pinfunction "1_1") (pintype "passive"))
    )
    (net (code "38") (name "/DDR_2_DQ12") (class "Default")
      (node (ref "IC19") (pin "M26") (pinfunction "IO_L24P_M5DQ12_5_M26") (pintype "bidirectional"))
      (node (ref "IC28") (pin "A7") (pinfunction "DQ12_A7") (pintype "bidirectional"))
      (node (ref "R302") (pin "1") (pinfunction "1_1") (pintype "passive"))
    )
    (net (code "39") (name "/DDR_2_DQ13") (class "Default")
      (node (ref "IC19") (pin "M27") (pinfunction "IO_L24N_M5DQ13_5_M27") (pintype "bidirectional"))
      (node (ref "IC28") (pin "A2") (pinfunction "DQ13_A2") (pintype "bidirectional"))
      (node (ref "R301") (pin "1") (pinfunction "1_1") (pintype "passive"))
    )
    (net (code "40") (name "/DDR_2_DQ14") (class "Default")
      (node (ref "IC19") (pin "M28") (pinfunction "IO_L25P_M5DQ14_5_M28") (pintype "bidirectional"))
      (node (ref "IC28") (pin "B8") (pinfunction "DQ14_B8") (pintype "bidirectional"))
      (node (ref "R300") (pin "1") (pinfunction "1_1") (pintype "passive"))
    )
    (net (code "41") (name "/DDR_2_DQ15") (class "Default")
      (node (ref "IC19") (pin "M30") (pinfunction "IO_L25N_M5DQ15_5_M30") (pintype "bidirectional"))
      (node (ref "IC28") (pin "A3") (pinfunction "DQ15_A3") (pintype "bidirectional"))
      (node (ref "R299") (pin "1") (pinfunction "1_1") (pintype "passive"))
    )
    (net (code "43") (name "/DDR_2_LDM") (class "Default")
      (node (ref "IC19") (pin "J28") (pinfunction "IO_L15N_M5LDM_5_J28") (pintype "bidirectional"))
      (node (ref "IC28") (pin "E7") (pinfunction "LDM_E7") (pintype "input"))
      (node (ref "R296") (pin "1") (pinfunction "1_1") (pintype "passive"))
    )
    (net (code "44") (name "/DDR_2_LDQS_N") (class "Default")
      (node (ref "IC19") (pin "J30") (pinfunction "IO_L18N_M5LDQSN_5_J30") (pintype "bidirectional"))
      (node (ref "IC28") (pin "G3") (pinfunction "LDQS_G3") (pintype "bidirectional"))
      (node (ref "R292") (pin "1") (pinfunction "1_1") (pintype "passive"))
    )
    (net (code "45") (name "/DDR_2_LDQS_P") (class "Default")
      (node (ref "IC19") (pin "J29") (pinfunction "IO_L18P_M5LDQS_5_J29") (pintype "bidirectional"))
      (node (ref "IC28") (pin "F3") (pinfunction "LDQS_F3") (pintype "bidirectional"))
      (node (ref "R294") (pin "1") (pinfunction "1_1") (pintype "passive"))
    )
    (net (code "46") (name "/DDR_2_ODT") (class "Default")
      (node (ref "IC19") (pin "E30") (pinfunction "IO_L12N_M5ODT_5_E30") (pintype "bidirectional"))
      (node (ref "IC28") (pin "K1") (pinfunction "ODT_K1") (pintype "input"))
      (node (ref "R270") (pin "2") (pinfunction "2_2") (pintype "passive"))
    )
    (net (code "47") (name "/DDR_2_RAS_N") (class "Default")
      (node (ref "IC19") (pin "K26") (pinfunction "IO_L14P_M5RASN_5_K26") (pintype "bidirectional"))
      (node (ref "IC28") (pin "J3") (pinfunction "RAS_J3") (pintype "input"))
      (node (ref "R266") (pin "1") (pinfunction "1_1") (pintype "passive"))
    )
    (net (code "48") (name "/DDR_2_RESET_N") (class "Default")
      (node (ref "IC19") (pin "C26") (pinfunction "IO_L3P_M5RESET_5_C26") (pintype "bidirectional"))
      (node (ref "IC28") (pin "T2") (pinfunction "RESET_T2") (pintype "input"))
      (node (ref "R278") (pin "2") (pinfunction "2_2") (pintype "passive"))
    )
    (net (code "49") (name "/DDR_2_UDM") (class "Default")
      (node (ref "IC19") (pin "J27") (pinfunction "IO_L15P_M5UDM_5_J27") (pintype "bidirectional"))
      (node (ref "IC28") (pin "D3") (pinfunction "UDM_D3") (pintype "input"))
      (node (ref "R298") (pin "1") (pinfunction "1_1") (pintype "passive"))
    )
    (net (code "50") (name "/DDR_2_UDQS_N") (class "Default")
      (node (ref "IC19") (pin "K30") (pinfunction "IO_L23N_M5UDQSN_5_K30") (pintype "bidirectional"))
      (node (ref "IC28") (pin "B7") (pinfunction "UDQS_B7") (pintype "bidirectional"))
      (node (ref "R293") (pin "1") (pinfunction "1_1") (pintype "passive"))
    )
    (net (code "51") (name "/DDR_2_UDQS_P") (class "Default")
      (node (ref "IC19") (pin "K28") (pinfunction "IO_L23P_M5UDQS_5_K28") (pintype "bidirectional"))
      (node (ref "IC28") (pin "C7") (pinfunction "UDQS_C7") (pintype "bidirectional"))
      (node (ref "R295") (pin "1") (pinfunction "1_1") (pintype "passive"))
    )
    (net (code "52") (name "/DDR_2_WE_N") (class "Default")
      (node (ref "IC19") (pin "E26") (pinfunction "IO_L7P_M5WE_5_E26") (pintype "bidirectional"))
      (node (ref "IC28") (pin "L3") (pinfunction "WE_L3") (pintype "input"))
      (node (ref "R264") (pin "1") (pinfunction "1_1") (pintype "passive"))
    )
    (net (code "53") (name "/DDR_2_ZQ") (class "Default")
      (node (ref "IC28") (pin "L8") (pinfunction "ZQ_L8") (pintype "input"))
      (node (ref "R180") (pin "2") (pinfunction "2_2") (pintype "passive"))
    )
    (net (code "54") (name "GND") (class "Default")
      (node (ref "C242") (pin "1") (pinfunction "1_1") (pintype "passive"))
      (node (ref "C243") (pin "1") (pinfunction "1_1") (pintype "passive"))
      (node (ref "C383") (pin "1") (pinfunction "1_1") (pintype "passive"))
      (node (ref "C384") (pin "1") (pinfunction "1_1") (pintype "passive"))
      (node (ref "C385") (pin "1") (pinfunction "1_1") (pintype "passive"))
      (node (ref "C388") (pin "1") (pinfunction "1_1") (pintype "passive"))
      (node (ref "C389") (pin "1") (pinfunction "1_1") (pintype "passive"))
      (node (ref "C391") (pin "1") (pinfunction "1_1") (pintype "passive"))
      (node (ref "C393") (pin "1") (pinfunction "1_1") (pintype "passive"))
      (node (ref "C394") (pin "1") (pinfunction "1_1") (pintype "passive"))
      (node (ref "C395") (pin "1") (pinfunction "1_1") (pintype "passive"))
      (node (ref "C396") (pin "1") (pinfunction "1_1") (pintype "passive"))
      (node (ref "C397") (pin "1") (pinfunction "1_1") (pintype "passive"))
      (node (ref "C398") (pin "1") (pinfunction "1_1") (pintype "passive"))
      (node (ref "C399") (pin "1") (pinfunction "1_1") (pintype "passive"))
      (node (ref "C400") (pin "1") (pinfunction "1_1") (pintype "passive"))
      (node (ref "C401") (pin "1") (pinfunction "1_1") (pintype "passive"))
      (node (ref "C402") (pin "1") (pinfunction "1_1") (pintype "passive"))
      (node (ref "C403") (pin "1") (pinfunction "1_1") (pintype "passive"))
      (node (ref "C404") (pin "1") (pinfunction "1_1") (pintype "passive"))
      (node (ref "C405") (pin "1") (pinfunction "1_1") (pintype "passive"))
      (node (ref "C406") (pin "1") (pinfunction "1_1") (pintype "passive"))
      (node (ref "IC28") (pin "A9") (pinfunction "VSS_A9") (pintype "power_in"))
      (node (ref "IC28") (pin "B1") (pinfunction "VSSQ_B1") (pintype "power_in"))
      (node (ref "IC28") (pin "B3") (pinfunction "VSS_B3") (pintype "power_in"))
      (node (ref "IC28") (pin "B9") (pinfunction "VSSQ_B9") (pintype "power_in"))
      (node (ref "IC28") (pin "D1") (pinfunction "VSSQ_D1") (pintype "power_in"))
      (node (ref "IC28") (pin "D8") (pinfunction "VSSQ_D8") (pintype "power_in"))
      (node (ref "IC28") (pin "E1") (pinfunction "VSS_E1") (pintype "power_in"))
      (node (ref "IC28") (pin "E2") (pinfunction "VSSQ_E2") (pintype "power_in"))
      (node (ref "IC28") (pin "E8") (pinfunction "VSSQ_E8") (pintype "power_in"))
      (node (ref "IC28") (pin "F9") (pinfunction "VSSQ_F9") (pintype "power_in"))
      (node (ref "IC28") (pin "G1") (pinfunction "VSSQ_G1") (pintype "power_in"))
      (node (ref "IC28") (pin "G8") (pinfunction "VSS_G8") (pintype "power_in"))
      (node (ref "IC28") (pin "G9") (pinfunction "VSSQ_G9") (pintype "power_in"))
      (node (ref "IC28") (pin "J2") (pinfunction "VSS_J2") (pintype "power_in"))
      (node (ref "IC28") (pin "J8") (pinfunction "VSS_J8") (pintype "power_in"))
      (node (ref "IC28") (pin "M1") (pinfunction "VSS_M1") (pintype "power_in"))
      (node (ref "IC28") (pin "M9") (pinfunction "VSS_M9") (pintype "power_in"))
      (node (ref "IC28") (pin "P1") (pinfunction "VSS_P1") (pintype "power_in"))
      (node (ref "IC28") (pin "P9") (pinfunction "VSS_P9") (pintype "power_in"))
      (node (ref "IC28") (pin "T1") (pinfunction "VSS_T1") (pintype "power_in"))
      (node (ref "IC28") (pin "T9") (pinfunction "VSS_T9") (pintype "power_in"))
      (node (ref "R127") (pin "2") (pinfunction "2_2") (pintype "passive"))
      (node (ref "R180") (pin "1") (pinfunction "1_1") (pintype "passive"))
      (node (ref "R268") (pin "2") (pinfunction "2_2") (pintype "passive"))
      (node (ref "R270") (pin "1") (pinfunction "1_1") (pintype "passive"))
      (node (ref "R278") (pin "1") (pinfunction "1_1") (pintype "passive"))
      (node (ref "R285") (pin "1") (pinfunction "1_1") (pintype "passive"))
    )
    (net (code "55") (name "Net-(IC19I-IO_L27N_5)") (class "Default")
      (node (ref "IC19") (pin "L25") (pinfunction "IO_L27N_5_L25") (pintype "bidirectional"))
      (node (ref "R127") (pin "1") (pinfunction "1_1") (pintype "passive"))
    )
    (net (code "56") (name "P1V5") (class "Default")
      (node (ref "C383") (pin "2") (pinfunction "2_2") (pintype "passive"))
      (node (ref "C384") (pin "2") (pinfunction "2_2") (pintype "passive"))
      (node (ref "C385") (pin "2") (pinfunction "2_2") (pintype "passive"))
      (node (ref "C388") (pin "2") (pinfunction "2_2") (pintype "passive"))
      (node (ref "C389") (pin "2") (pinfunction "2_2") (pintype "passive"))
      (node (ref "C391") (pin "2") (pinfunction "2_2") (pintype "passive"))
      (node (ref "C394") (pin "2") (pinfunction "2_2") (pintype "passive"))
      (node (ref "C395") (pin "2") (pinfunction "2_2") (pintype "passive"))
      (node (ref "C396") (pin "2") (pinfunction "2_2") (pintype "passive"))
      (node (ref "IC28") (pin "A1") (pinfunction "VDDQ_A1") (pintype "power_in"))
      (node (ref "IC28") (pin "A8") (pinfunction "VDDQ_A8") (pintype "power_in"))
      (node (ref "IC28") (pin "B2") (pinfunction "VDD_B2") (pintype "power_in"))
      (node (ref "IC28") (pin "C1") (pinfunction "VDDQ_C1") (pintype "power_in"))
      (node (ref "IC28") (pin "C9") (pinfunction "VDDQ_C9") (pintype "power_in"))
      (node (ref "IC28") (pin "D2") (pinfunction "VDDQ_D2") (pintype "power_in"))
      (node (ref "IC28") (pin "D9") (pinfunction "VDD_D9") (pintype "power_in"))
      (node (ref "IC28") (pin "E9") (pinfunction "VDDQ_E9") (pintype "power_in"))
      (node (ref "IC28") (pin "F1") (pinfunction "VDDQ_F1") (pintype "power_in"))
      (node (ref "IC28") (pin "G7") (pinfunction "VDD_G7") (pintype "power_in"))
      (node (ref "IC28") (pin "H2") (pinfunction "VDDQ_H2") (pintype "power_in"))
      (node (ref "IC28") (pin "H9") (pinfunction "VDDQ_H9") (pintype "power_in"))
      (node (ref "IC28") (pin "K2") (pinfunction "VDD_K2") (pintype "power_in"))
      (node (ref "IC28") (pin "K8") (pinfunction "VDD_K8") (pintype "power_in"))
      (node (ref "IC28") (pin "N1") (pinfunction "VDD_N1") (pintype "power_in"))
      (node (ref "IC28") (pin "N9") (pinfunction "VDD_N9") (pintype "power_in"))
      (node (ref "IC28") (pin "R1") (pinfunction "VDD_R1") (pintype "power_in"))
      (node (ref "IC28") (pin "R9") (pinfunction "VDD_R9") (pintype "power_in"))
    )
    (net (code "57") (name "VREF_DDR3") (class "Default")
      (node (ref "C242") (pin "2") (pinfunction "2_2") (pintype "passive"))
      (node (ref "C243") (pin "2") (pinfunction "2_2") (pintype "passive"))
      (node (ref "C393") (pin "2") (pinfunction "2_2") (pintype "passive"))
      (node (ref "IC19") (pin "F25") (pinfunction "IO_L1N_A24_VREF_5_F25") (pintype "bidirectional"))
      (node (ref "IC19") (pin "N25") (pinfunction "IO_L26N_VREF_5_N25") (pintype "bidirectional"))
      (node (ref "IC28") (pin "H1") (pinfunction "VREFDQ_H1") (pintype "power_in"))
      (node (ref "IC28") (pin "M8") (pinfunction "VREFCA_M8") (pintype "power_in"))
    )
    (net (code "58") (name "VTT_DDR3") (class "Default")
      (node (ref "C397") (pin "2") (pinfunction "2_2") (pintype "passive"))
      (node (ref "C398") (pin "2") (pinfunction "2_2") (pintype "passive"))
      (node (ref "C399") (pin "2") (pinfunction "2_2") (pintype "passive"))
      (node (ref "C400") (pin "2") (pinfunction "2_2") (pintype "passive"))
      (node (ref "C401") (pin "2") (pinfunction "2_2") (pintype "passive"))
      (node (ref "C402") (pin "2") (pinfunction "2_2") (pintype "passive"))
      (node (ref "C403") (pin "2") (pinfunction "2_2") (pintype "passive"))
      (node (ref "C404") (pin "2") (pinfunction "2_2") (pintype "passive"))
      (node (ref "C405") (pin "2") (pinfunction "2_2") (pintype "passive"))
      (node (ref "C406") (pin "2") (pinfunction "2_2") (pintype "passive"))
      (node (ref "R181") (pin "2") (pinfunction "2_2") (pintype "passive"))
      (node (ref "R182") (pin "2") (pinfunction "2_2") (pintype "passive"))
      (node (ref "R261") (pin "2") (pinfunction "2_2") (pintype "passive"))
      (node (ref "R264") (pin "2") (pinfunction "2_2") (pintype "passive"))
      (node (ref "R265") (pin "2") (pinfunction "2_2") (pintype "passive"))
      (node (ref "R266") (pin "2") (pinfunction "2_2") (pintype "passive"))
      (node (ref "R267") (pin "2") (pinfunction "2_2") (pintype "passive"))
      (node (ref "R269") (pin "2") (pinfunction "2_2") (pintype "passive"))
      (node (ref "R271") (pin "2") (pinfunction "2_2") (pintype "passive"))
      (node (ref "R272") (pin "2") (pinfunction "2_2") (pintype "passive"))
      (node (ref "R273") (pin "2") (pinfunction "2_2") (pintype "passive"))
      (node (ref "R280") (pin "2") (pinfunction "2_2") (pintype "passive"))
      (node (ref "R281") (pin "2") (pinfunction "2_2") (pintype "passive"))
      (node (ref "R282") (pin "2") (pinfunction "2_2") (pintype "passive"))
      (node (ref "R283") (pin "2") (pinfunction "2_2") (pintype "passive"))
      (node (ref "R284") (pin "2") (pinfunction "2_2") (pintype "passive"))
      (node (ref "R287") (pin "2") (pinfunction "2_2") (pintype "passive"))
      (node (ref "R288") (pin "2") (pinfunction "2_2") (pintype "passive"))
      (node (ref "R289") (pin "2") (pinfunction "2_2") (pintype "passive"))
      (node (ref "R290") (pin "2") (pinfunction "2_2") (pintype "passive"))
      (node (ref "R292") (pin "2") (pinfunction "2_2") (pintype "passive"))
      (node (ref "R293") (pin "2") (pinfunction "2_2") (pintype "passive"))
      (node (ref "R294") (pin "2") (pinfunction "2_2") (pintype "passive"))
      (node (ref "R295") (pin "2") (pinfunction "2_2") (pintype "passive"))
      (node (ref "R296") (pin "2") (pinfunction "2_2") (pintype "passive"))
      (node (ref "R297") (pin "2") (pinfunction "2_2") (pintype "passive"))
      (node (ref "R298") (pin "2") (pinfunction "2_2") (pintype "passive"))
      (node (ref "R299") (pin "2") (pinfunction "2_2") (pintype "passive"))
      (node (ref "R300") (pin "2") (pinfunction "2_2") (pintype "passive"))
      (node (ref "R301") (pin "2") (pinfunction "2_2") (pintype "passive"))
      (node (ref "R302") (pin "2") (pinfunction "2_2") (pintype "passive"))
      (node (ref "R303") (pin "2") (pinfunction "2_2") (pintype "passive"))
      (node (ref "R304") (pin "2") (pinfunction "2_2") (pintype "passive"))
      (node (ref "R305") (pin "2") (pinfunction "2_2") (pintype "passive"))
      (node (ref "R306") (pin "2") (pinfunction "2_2") (pintype "passive"))
      (node (ref "R307") (pin "2") (pinfunction "2_2") (pintype "passive"))
      (node (ref "R308") (pin "2") (pinfunction "2_2") (pintype "passive"))
      (node (ref "R309") (pin "2") (pinfunction "2_2") (pintype "passive"))
      (node (ref "R310") (pin "2") (pinfunction "2_2") (pintype "passive"))
      (node (ref "R311") (pin "2") (pinfunction "2_2") (pintype "passive"))
      (node (ref "R312") (pin "2") (pinfunction "2_2") (pintype "passive"))
      (node (ref "R313") (pin "2") (pinfunction "2_2") (pintype "passive"))
      (node (ref "R314") (pin "2") (pinfunction "2_2") (pintype "passive"))
    )
    (net (code "59") (name "unconnected-(IC19I-IO_L1P_A25_5-PadG25)") (class "Default")
      (node (ref "IC19") (pin "G25") (pinfunction "IO_L1P_A25_5_G25") (pintype "bidirectional+no_connect"))
    )
    (net (code "60") (name "unconnected-(IC19I-IO_L26P_5-PadN24)") (class "Default")
      (node (ref "IC19") (pin "N24") (pinfunction "IO_L26P_5_N24") (pintype "bidirectional"))
    )
    (net (code "61") (name "unconnected-(IC19I-IO_L27P_5-PadL24)") (class "Default")
      (node (ref "IC19") (pin "L24") (pinfunction "IO_L27P_5_L24") (pintype "bidirectional"))
    )
    (net (code "62") (name "unconnected-(IC28-NC-PadJ1)") (class "Default")
      (node (ref "IC28") (pin "J1") (pinfunction "NC_J1") (pintype "passive+no_connect"))
    )
    (net (code "63") (name "unconnected-(IC28-NC-PadJ9)") (class "Default")
      (node (ref "IC28") (pin "J9") (pinfunction "NC_J9") (pintype "passive+no_connect"))
    )
    (net (code "64") (name "unconnected-(IC28-NC-PadL1)") (class "Default")
      (node (ref "IC28") (pin "L1") (pinfunction "NC_L1") (pintype "passive+no_connect"))
    )
    (net (code "65") (name "unconnected-(IC28-NC-PadL9)") (class "Default")
      (node (ref "IC28") (pin "L9") (pinfunction "NC_L9") (pintype "passive+no_connect"))
    )
    (net (code "66") (name "unconnected-(IC28-NC-PadM7)") (class "Default")
      (node (ref "IC28") (pin "M7") (pinfunction "NC_M7") (pintype "passive+no_connect"))
    )
  )
)
